# SparkFun_Si7021_Breakout.net
KiCad netlist of a schematic drawn in EAGLE
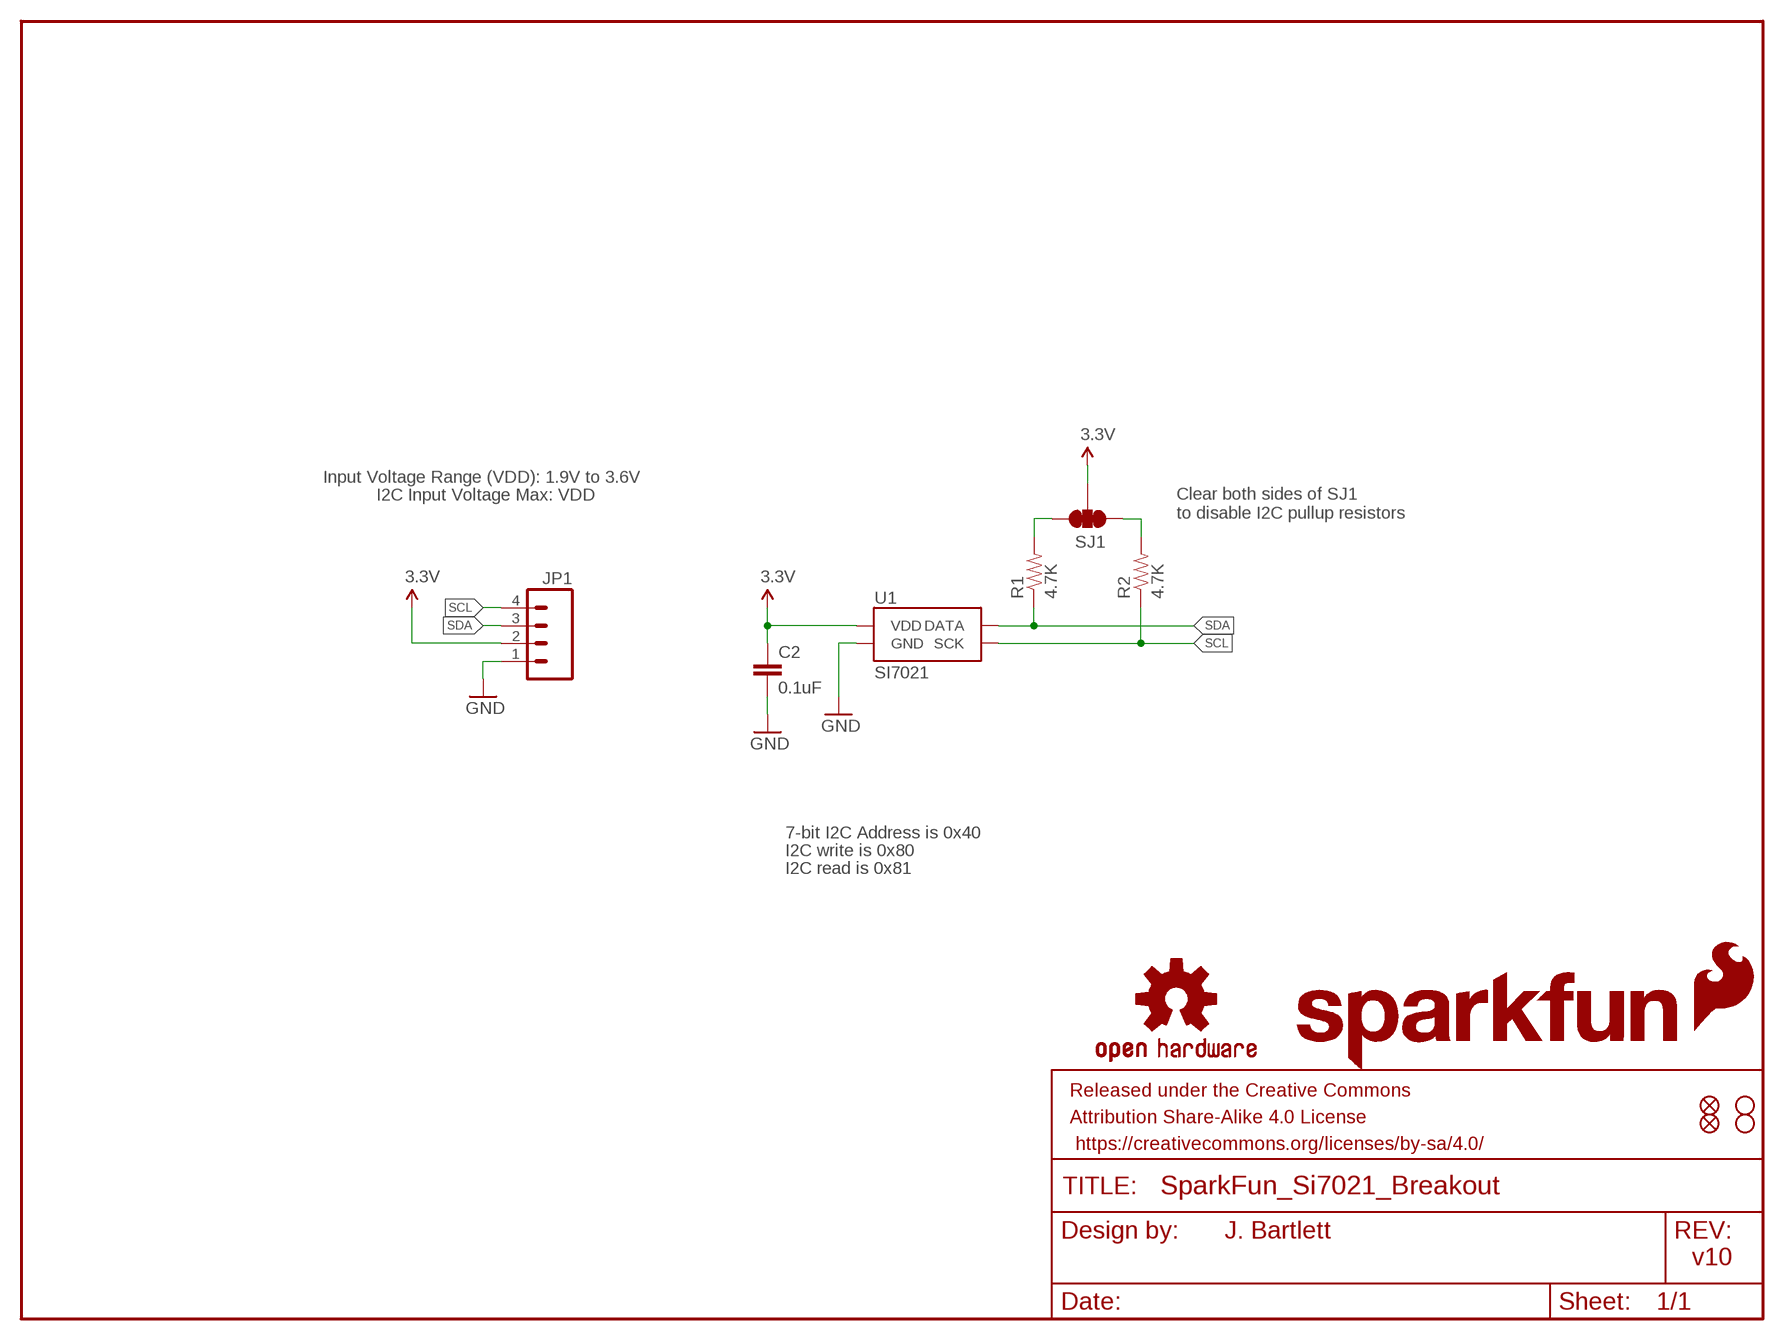
[diagram p0: schematic, sheet 1]

(export (version "E")
  (design (tool "Eeschema 10.0.6"))
  (components
    (comp (ref "C2")
      (value "0.1uF")
      (footprint "eagle-import:0603-CAP")
      (libsource (lib "eagle-import") (part "0.1UF-25V(+80/-20%)(0603)"))
    )
    (comp (ref "FRAME2")
      (value "FRAME-LETTER")
      (footprint "eagle-import:CREATIVE_COMMONS")
      (libsource (lib "eagle-import") (part "FRAME-LETTER"))
    )
    (comp (ref "JP1")
      (value "M04PTH")
      (footprint "eagle-import:1X04")
      (libsource (lib "eagle-import") (part "M04PTH"))
    )
    (comp (ref "JP3")
      (value "FIDUCIALUFIDUCIAL")
      (footprint "eagle-import:MICRO-FIDUCIAL")
      (libsource (lib "eagle-import") (part "FIDUCIALUFIDUCIAL"))
    )
    (comp (ref "JP4")
      (value "FIDUCIALUFIDUCIAL")
      (footprint "eagle-import:MICRO-FIDUCIAL")
      (libsource (lib "eagle-import") (part "FIDUCIALUFIDUCIAL"))
    )
    (comp (ref "LOGO2")
      (value "OSHW-LOGOS")
      (footprint "eagle-import:OSHW-LOGO-S")
      (libsource (lib "eagle-import") (part "OSHW-LOGOS"))
    )
    (comp (ref "LOGO3")
      (value "SFE_LOGO_FLAME.1_INCH")
      (footprint "eagle-import:SFE_LOGO_FLAME_.1")
      (libsource (lib "eagle-import") (part "SFE_LOGO_FLAME.1_INCH"))
    )
    (comp (ref "LOGO4")
      (value "SFE_LOGO_NAME.1_INCH")
      (footprint "eagle-import:SFE_LOGO_NAME_.1")
      (libsource (lib "eagle-import") (part "SFE_LOGO_NAME.1_INCH"))
    )
    (comp (ref "R1")
      (value "4.7K")
      (footprint "eagle-import:0603-RES")
      (libsource (lib "eagle-import") (part "4.7KOHM-1/10W-1%(0603)"))
    )
    (comp (ref "R2")
      (value "4.7K")
      (footprint "eagle-import:0603-RES")
      (libsource (lib "eagle-import") (part "4.7KOHM-1/10W-1%(0603)"))
    )
    (comp (ref "SJ1")
      (value "SOLDERJUMPER_2WAYPASTE1&2&3")
      (footprint "eagle-import:SJ_3_PASTE1&2&3")
      (libsource (lib "eagle-import") (part "SOLDERJUMPER_2WAYPASTE1&2&3"))
    )
    (comp (ref "STANDOFF1")
      (value "STAND-OFF")
      (footprint "eagle-import:STAND-OFF")
      (libsource (lib "eagle-import") (part "STAND-OFF"))
    )
    (comp (ref "STANDOFF2")
      (value "STAND-OFF")
      (footprint "eagle-import:STAND-OFF")
      (libsource (lib "eagle-import") (part "STAND-OFF"))
    )
    (comp (ref "U1")
      (value "SI7021")
      (footprint "eagle-import:SI7021")
      (libsource (lib "eagle-import") (part "SI7021"))
    )
  )
  (nets
    (net (code "1") (name "3.3V") (class "Default")
      (node (ref "C2") (pin "1") (pinfunction "1_1") (pintype "passive"))
      (node (ref "JP1") (pin "2") (pinfunction "2_2") (pintype "passive"))
      (node (ref "SJ1") (pin "2") (pinfunction "2_2") (pintype "passive"))
      (node (ref "U1") (pin "VDD") (pinfunction "VDD_VDD") (pintype "power_in"))
    )
    (net (code "2") (name "GND") (class "Default")
      (node (ref "C2") (pin "2") (pinfunction "2_2") (pintype "passive"))
      (node (ref "JP1") (pin "1") (pinfunction "1_1") (pintype "passive"))
      (node (ref "U1") (pin "GND") (pinfunction "GND_GND") (pintype "power_in"))
    )
    (net (code "3") (name "Net-(R1-Pad2)") (class "Default")
      (node (ref "R1") (pin "2") (pinfunction "2_2") (pintype "passive"))
      (node (ref "SJ1") (pin "3") (pinfunction "3_3") (pintype "passive"))
    )
    (net (code "4") (name "Net-(R2-Pad2)") (class "Default")
      (node (ref "R2") (pin "2") (pinfunction "2_2") (pintype "passive"))
      (node (ref "SJ1") (pin "1") (pinfunction "1_1") (pintype "passive"))
    )
    (net (code "5") (name "SCL") (class "Default")
      (node (ref "JP1") (pin "4") (pinfunction "4_4") (pintype "passive"))
      (node (ref "R2") (pin "1") (pinfunction "1_1") (pintype "passive"))
      (node (ref "U1") (pin "SCK") (pinfunction "SCK_SCK") (pintype "input"))
    )
    (net (code "6") (name "SDA") (class "Default")
      (node (ref "JP1") (pin "3") (pinfunction "3_3") (pintype "passive"))
      (node (ref "R1") (pin "1") (pinfunction "1_1") (pintype "passive"))
      (node (ref "U1") (pin "DATA") (pinfunction "DATA_DATA") (pintype "bidirectional"))
    )
  )
)
